# DAC8830V1_0.net
KiCad netlist of a schematic drawn in Altium Designer
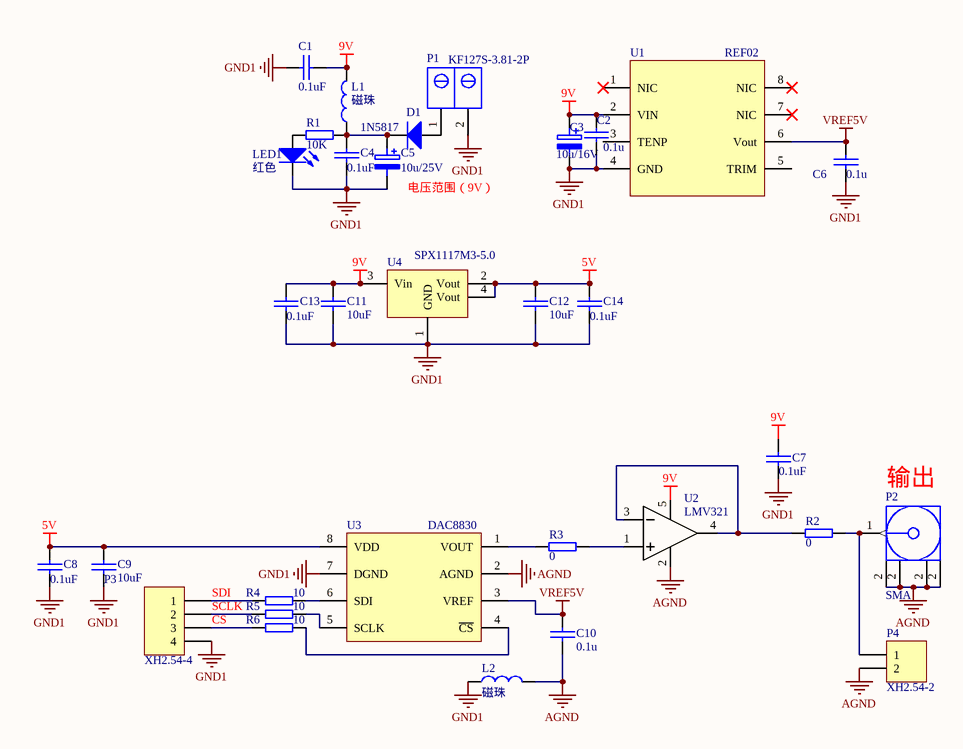
[diagram p0: DAC8830V1.0.schdoc]

(export (version "E")
  (design (tool "Eeschema 10.0.6"))
  (components
    (comp (ref "C1")
      (value "0.1uF")
      (footprint "0805")
      (libsource (lib "Sch_Device_veryaz") (part "电容 贴片 0805"))
    )
    (comp (ref "C2")
      (value "0.1u")
      (footprint "0805")
      (libsource (lib "Sch_Device_veryaz") (part "电容 贴片 0805"))
    )
    (comp (ref "C3")
      (value "10u/16V")
      (footprint "1206")
      (libsource (lib "Sch_Device_veryaz") (part "电容 贴片 铝电解100u/25V"))
    )
    (comp (ref "C4")
      (value "0.1uF")
      (footprint "0805")
      (libsource (lib "Sch_Device_veryaz") (part "电容 贴片 0805"))
    )
    (comp (ref "C5")
      (value "10u/25V")
      (footprint "1206")
      (libsource (lib "Sch_Device_veryaz") (part "电容 贴片 铝电解100u/25V"))
    )
    (comp (ref "C6")
      (value "0.1u")
      (footprint "0805")
      (libsource (lib "Sch_Device_veryaz") (part "电容 贴片 0805"))
    )
    (comp (ref "C7")
      (value "0.1uF")
      (footprint "0805")
      (libsource (lib "Sch_Device_veryaz") (part "电容 贴片 0805"))
    )
    (comp (ref "C8")
      (value "0.1uF")
      (footprint "0805")
      (libsource (lib "Sch_Device_veryaz") (part "电容 贴片 0805"))
    )
    (comp (ref "C9")
      (value "10uF")
      (footprint "1206")
      (libsource (lib "Sch_Device_veryaz") (part "电容 贴片 0805"))
    )
    (comp (ref "C10")
      (value "0.1u")
      (footprint "0805")
      (libsource (lib "Sch_Device_veryaz") (part "电容 贴片 0805"))
    )
    (comp (ref "C11")
      (value "10uF")
      (footprint "1206")
      (libsource (lib "Sch_Device_veryaz") (part "电容 贴片 0805"))
    )
    (comp (ref "C12")
      (value "10uF")
      (footprint "1206")
      (libsource (lib "Sch_Device_veryaz") (part "电容 贴片 0805"))
    )
    (comp (ref "C13")
      (value "0.1uF")
      (footprint "0805")
      (libsource (lib "Sch_Device_veryaz") (part "电容 贴片 0805"))
    )
    (comp (ref "C14")
      (value "0.1uF")
      (footprint "0805")
      (libsource (lib "Sch_Device_veryaz") (part "电容 贴片 0805"))
    )
    (comp (ref "D1")
      (value "1N5817")
      (footprint "二极管 贴片 2010")
      (libsource (lib "Sch_Device_veryaz") (part "二极管 贴片1N5817"))
    )
    (comp (ref "L1") (value "磁珠") (footprint "0805") (libsource (lib "Sch_Device_veryaz") (part "磁珠")))
    (comp (ref "L2") (value "磁珠") (footprint "0805") (libsource (lib "") (part "磁珠_1")))
    (comp (ref "LED1")
      (value "红色")
      (footprint "LED0805")
      (libsource (lib "Sch_Device_veryaz") (part "二极管 贴片发光 0805"))
    )
    (comp (ref "P1")
      (value "KF127S-3.81-2P")
      (footprint "KF127S-3.81-2P")
      (libsource (lib "Sch_Device_veryaz") (part "连接件 KF127S-3.81-2P"))
    )
    (comp (ref "P2")
      (value "SMA")
      (footprint "天线座 50ohm 侧卧")
      (libsource (lib "Sch_Device_veryaz") (part "联结件 天线座 SMA"))
    )
    (comp (ref "P3")
      (value "XH2.54-4")
      (footprint "VH2.54_4")
      (libsource (lib "Sch_Device_veryaz") (part "连接件 XH2.54-4"))
    )
    (comp (ref "P4")
      (value "XH2.54-2")
      (footprint "VH2.54_2")
      (libsource (lib "Sch_Device_veryaz") (part "连接件 XH2.54-2"))
    )
    (comp (ref "R1")
      (value "10K")
      (footprint "0805")
      (libsource (lib "Sch_Device_veryaz") (part "电阻 贴片 0805"))
    )
    (comp (ref "R2") (value "0") (footprint "0805") (libsource (lib "Sch_Device_veryaz") (part "电阻 贴片 0805")))
    (comp (ref "R3") (value "0") (footprint "0805") (libsource (lib "") (part "电阻 贴片 0805_1")))
    (comp (ref "R4") (value "10") (footprint "0805") (libsource (lib "") (part "电阻 贴片 0805_1")))
    (comp (ref "R5") (value "10") (footprint "0805") (libsource (lib "") (part "电阻 贴片 0805_1")))
    (comp (ref "R6") (value "10") (footprint "0805") (libsource (lib "") (part "电阻 贴片 0805_1")))
    (comp (ref "U1")
      (value "REF02")
      (footprint "SOIC8")
      (libsource (lib "Sch_Device_veryaz") (part "贴片芯片 ADR02"))
    )
    (comp (ref "U2")
      (value "LMV321")
      (footprint "SOT23-5")
      (libsource (lib "Sch_Device_veryaz") (part "贴片芯片 LMV321"))
    )
    (comp (ref "U3")
      (value "DAC8830")
      (footprint "soic8")
      (libsource (lib "Sch_Device_veryaz") (part "贴片芯片 DAC8830"))
    )
    (comp (ref "U4")
      (value "SPX1117M3-5.0")
      (footprint "SOT223")
      (description "LDO")
      (libsource (lib "Sch_Device_veryaz") (part "贴片芯片 SPX1117M3-5.0"))
    )
  )
  (nets
    (net (code "1") (name "/CS") (class "Default")
      (node (ref "P3") (pin "3") (pinfunction "3_3") (pintype "passive"))
      (node (ref "R6") (pin "2") (pinfunction "2_2") (pintype "passive"))
    )
    (net (code "2") (name "/SCLK") (class "Default")
      (node (ref "P3") (pin "2") (pinfunction "2_2") (pintype "passive"))
      (node (ref "R5") (pin "2") (pinfunction "2_2") (pintype "passive"))
    )
    (net (code "3") (name "/SDI") (class "Default")
      (node (ref "P3") (pin "1") (pinfunction "1_1") (pintype "passive"))
      (node (ref "R4") (pin "2") (pinfunction "2_2") (pintype "passive"))
    )
    (net (code "4") (name "5V") (class "Default")
      (node (ref "C12") (pin "2") (pintype "passive"))
      (node (ref "C14") (pin "2") (pintype "passive"))
      (node (ref "C8") (pin "2") (pintype "passive"))
      (node (ref "C9") (pin "2") (pintype "passive"))
      (node (ref "U3") (pin "8") (pinfunction "VDD_8") (pintype "passive"))
      (node (ref "U4") (pin "2") (pinfunction "Vout_2") (pintype "passive"))
      (node (ref "U4") (pin "4") (pinfunction "Vout_4") (pintype "passive"))
    )
    (net (code "5") (name "9V") (class "Default")
      (node (ref "C1") (pin "1") (pintype "passive"))
      (node (ref "C11") (pin "2") (pintype "passive"))
      (node (ref "C13") (pin "2") (pintype "passive"))
      (node (ref "C2") (pin "1") (pintype "passive"))
      (node (ref "C3") (pin "1") (pintype "passive"))
      (node (ref "C7") (pin "2") (pintype "passive"))
      (node (ref "L1") (pin "2") (pinfunction "2_2") (pintype "passive"))
      (node (ref "U1") (pin "2") (pinfunction "VIN_2") (pintype "passive"))
      (node (ref "U2") (pin "5") (pinfunction "VCC_5") (pintype "passive"))
      (node (ref "U4") (pin "3") (pinfunction "Vin_3") (pintype "passive"))
    )
    (net (code "6") (name "AGND") (class "Default")
      (node (ref "C10") (pin "2") (pintype "passive"))
      (node (ref "L2") (pin "2") (pinfunction "2_2") (pintype "passive"))
      (node (ref "P2") (pin "2") (pinfunction "2_2") (pintype "power_in"))
      (node (ref "P4") (pin "2") (pinfunction "2_2") (pintype "passive"))
      (node (ref "U2") (pin "2") (pinfunction "GND_2") (pintype "passive"))
      (node (ref "U3") (pin "2") (pinfunction "AGND_2") (pintype "passive"))
    )
    (net (code "7") (name "GND1") (class "Default")
      (node (ref "C1") (pin "2") (pintype "passive"))
      (node (ref "C11") (pin "1") (pintype "passive"))
      (node (ref "C12") (pin "1") (pintype "passive"))
      (node (ref "C13") (pin "1") (pintype "passive"))
      (node (ref "C14") (pin "1") (pintype "passive"))
      (node (ref "C2") (pin "2") (pintype "passive"))
      (node (ref "C3") (pin "2") (pintype "passive"))
      (node (ref "C4") (pin "1") (pintype "passive"))
      (node (ref "C5") (pin "2") (pintype "passive"))
      (node (ref "C6") (pin "2") (pintype "passive"))
      (node (ref "C7") (pin "1") (pintype "passive"))
      (node (ref "C8") (pin "1") (pintype "passive"))
      (node (ref "C9") (pin "1") (pintype "passive"))
      (node (ref "L2") (pin "1") (pinfunction "1_1") (pintype "passive"))
      (node (ref "LED1") (pin "2") (pinfunction "K_2") (pintype "passive"))
      (node (ref "P1") (pin "2") (pinfunction "2_2") (pintype "passive"))
      (node (ref "P3") (pin "4") (pinfunction "4_4") (pintype "passive"))
      (node (ref "U1") (pin "4") (pinfunction "GND_4") (pintype "passive"))
      (node (ref "U3") (pin "7") (pinfunction "DGND_7") (pintype "passive"))
      (node (ref "U4") (pin "1") (pinfunction "GND_1") (pintype "passive"))
    )
    (net (code "8") (name "Net-(D1-A)") (class "Default")
      (node (ref "D1") (pin "1") (pinfunction "A_1") (pintype "passive"))
      (node (ref "P1") (pin "1") (pinfunction "1_1") (pintype "passive"))
    )
    (net (code "9") (name "Net-(D1-K)") (class "Default")
      (node (ref "C4") (pin "2") (pintype "passive"))
      (node (ref "C5") (pin "1") (pintype "passive"))
      (node (ref "D1") (pin "2") (pinfunction "K_2") (pintype "passive"))
      (node (ref "L1") (pin "1") (pinfunction "1_1") (pintype "passive"))
      (node (ref "R1") (pin "2") (pinfunction "2_2") (pintype "passive"))
    )
    (net (code "10") (name "Net-(LED1-A)") (class "Default")
      (node (ref "LED1") (pin "1") (pinfunction "A_1") (pintype "passive"))
      (node (ref "R1") (pin "1") (pinfunction "1_1") (pintype "passive"))
    )
    (net (code "11") (name "Net-(P2-Signal)") (class "Default")
      (node (ref "P2") (pin "1") (pinfunction "Signal_1") (pintype "output"))
      (node (ref "P4") (pin "1") (pinfunction "1_1") (pintype "passive"))
      (node (ref "R2") (pin "2") (pinfunction "2_2") (pintype "passive"))
    )
    (net (code "12") (name "Net-(U2-IN+)") (class "Default")
      (node (ref "R3") (pin "1") (pinfunction "1_1") (pintype "passive"))
      (node (ref "U2") (pin "1") (pinfunction "IN+_1") (pintype "passive"))
    )
    (net (code "13") (name "Net-(U2-IN-)") (class "Default")
      (node (ref "R2") (pin "1") (pinfunction "1_1") (pintype "passive"))
      (node (ref "U2") (pin "3") (pinfunction "IN-_3") (pintype "passive"))
      (node (ref "U2") (pin "4") (pinfunction "OUT_4") (pintype "passive"))
    )
    (net (code "14") (name "Net-(U3-SCLK)") (class "Default")
      (node (ref "R5") (pin "1") (pinfunction "1_1") (pintype "passive"))
      (node (ref "U3") (pin "5") (pinfunction "SCLK_5") (pintype "passive"))
    )
    (net (code "15") (name "Net-(U3-SDI)") (class "Default")
      (node (ref "R4") (pin "1") (pinfunction "1_1") (pintype "passive"))
      (node (ref "U3") (pin "6") (pinfunction "SDI_6") (pintype "passive"))
    )
    (net (code "16") (name "Net-(U3-VOUT)") (class "Default")
      (node (ref "R3") (pin "2") (pinfunction "2_2") (pintype "passive"))
      (node (ref "U3") (pin "1") (pinfunction "VOUT_1") (pintype "passive"))
    )
    (net (code "17") (name "Net-(U3-~{CS})") (class "Default")
      (node (ref "R6") (pin "1") (pinfunction "1_1") (pintype "passive"))
      (node (ref "U3") (pin "4") (pinfunction "~{CS}_4") (pintype "passive"))
    )
    (net (code "18") (name "VREF5V") (class "Default")
      (node (ref "C10") (pin "1") (pintype "passive"))
      (node (ref "C6") (pin "1") (pintype "passive"))
      (node (ref "U1") (pin "6") (pinfunction "Vout_6") (pintype "passive"))
      (node (ref "U3") (pin "3") (pinfunction "VREF_3") (pintype "passive"))
    )
    (net (code "19") (name "unconnected-(U1-NIC-Pad1)") (class "Default")
      (node (ref "U1") (pin "1") (pinfunction "NIC_1") (pintype "passive+no_connect"))
    )
    (net (code "20") (name "unconnected-(U1-NIC-Pad7)") (class "Default")
      (node (ref "U1") (pin "7") (pinfunction "NIC_7") (pintype "passive+no_connect"))
    )
    (net (code "21") (name "unconnected-(U1-NIC-Pad8)") (class "Default")
      (node (ref "U1") (pin "8") (pinfunction "NIC_8") (pintype "passive+no_connect"))
    )
    (net (code "22") (name "unconnected-(U1-TENP-Pad3)") (class "Default")
      (node (ref "U1") (pin "3") (pinfunction "TENP_3") (pintype "passive"))
    )
    (net (code "23") (name "unconnected-(U1-TRIM-Pad5)") (class "Default")
      (node (ref "U1") (pin "5") (pinfunction "TRIM_5") (pintype "passive"))
    )
  )
)
